# ttl.net
KiCad netlist of a schematic drawn in Altium Designer
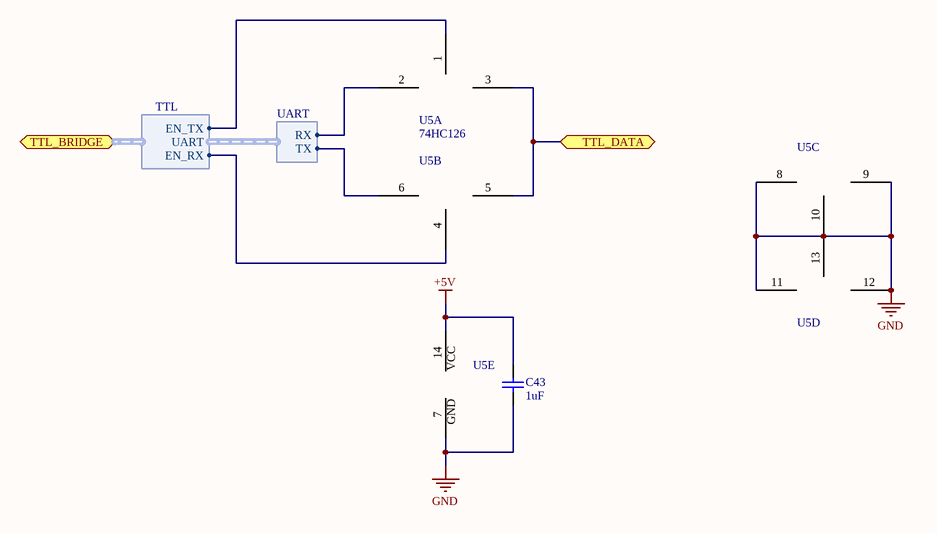
[diagram p0: ttl.SchDoc]

(export (version "E")
  (design (tool "Eeschema 10.0.6"))
  (components
    (comp (ref "C43")
      (value "1uF")
      (footprint "C2012")
      (description "Capacitor")
      (fields
        (field (name "MANUFACTURER") "MULTICOMP")
        (field (name "MANUFACTURER PART NUMBER") "MC0805B105K250CT")
        (field (name "PUBLISHER") "Altium Limited")
      )
      (libsource (lib "Miscellaneous Devices") (part "Cap"))
    )
    (comp (ref "U5")
      (value "74HC126")
      (footprint "SOIC14")
      (description "Quad 3-State Noninverting Buffer")
      (fields (field (name "MANUFACTURER") "NXP") (field (name "MANUFACTURER PART NUMBER") "74HC126D"))
      (libsource (lib "bitbots") (part "74HC126"))
    )
  )
  (nets
    (net (code "3") (name "+5V") (class "Default")
      (node (ref "C43") (pin "1") (pinfunction "1_1") (pintype "passive"))
      (node (ref "U5") (pin "14") (pinfunction "VCC_14") (pintype "power_in"))
    )
    (net (code "4") (name "/EN_RX") (class "Default")
      (node (ref "U5") (pin "4") (pinfunction "OE2_4") (pintype "passive"))
    )
    (net (code "5") (name "/EN_TX") (class "Default")
      (node (ref "U5") (pin "1") (pinfunction "OE1_1") (pintype "passive"))
    )
    (net (code "6") (name "/RX") (class "Default")
      (node (ref "U5") (pin "2") (pinfunction "A1_2") (pintype "passive"))
    )
    (net (code "8") (name "/TTL_DATA") (class "Default")
      (node (ref "U5") (pin "3") (pinfunction "Y1_3") (pintype "passive"))
      (node (ref "U5") (pin "5") (pinfunction "A2_5") (pintype "passive"))
    )
    (net (code "9") (name "/TX") (class "Default")
      (node (ref "U5") (pin "6") (pinfunction "Y2_6") (pintype "passive"))
    )
    (net (code "11") (name "GND") (class "Default")
      (node (ref "C43") (pin "2") (pinfunction "2_2") (pintype "passive"))
      (node (ref "U5") (pin "10") (pinfunction "OE3_10") (pintype "passive"))
      (node (ref "U5") (pin "11") (pinfunction "Y4_11") (pintype "passive"))
      (node (ref "U5") (pin "12") (pinfunction "A4_12") (pintype "passive"))
      (node (ref "U5") (pin "13") (pinfunction "OE4_13") (pintype "passive"))
      (node (ref "U5") (pin "7") (pinfunction "GND_7") (pintype "power_in"))
      (node (ref "U5") (pin "8") (pinfunction "Y3_8") (pintype "passive"))
      (node (ref "U5") (pin "9") (pinfunction "A3_9") (pintype "passive"))
    )
  )
)
